# Linear_scale_digitizer.net
KiCad netlist of a schematic drawn in EAGLE
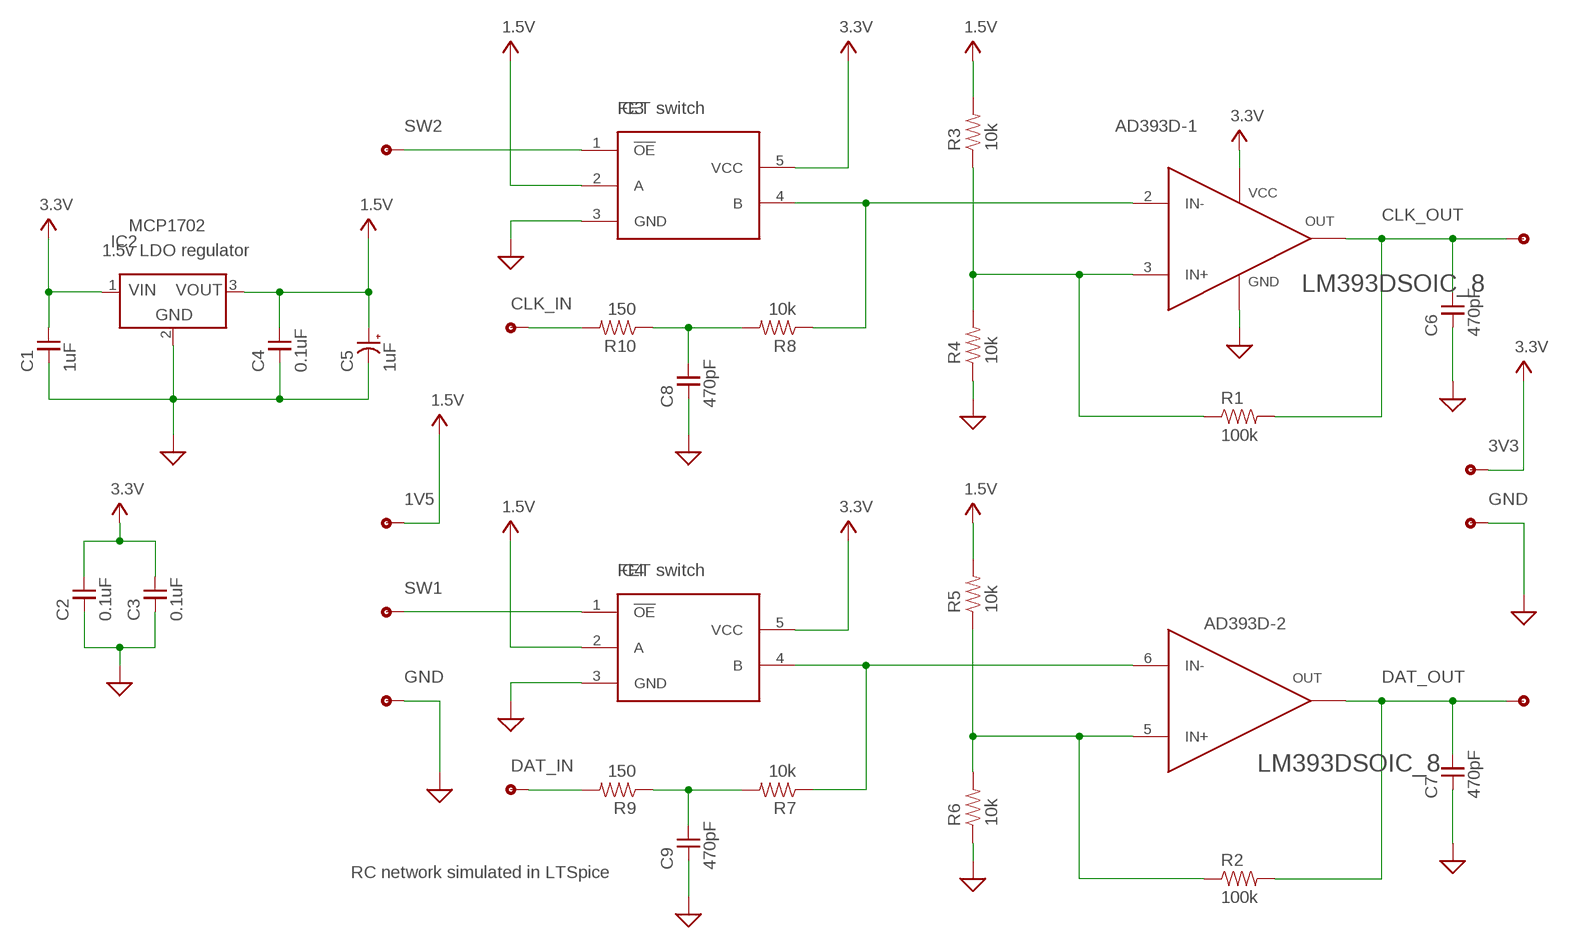
[diagram p0: schematic, sheet 1]

(export (version "E")
  (design (tool "Eeschema 10.0.6"))
  (components
    (comp (ref "C1")
      (value "1uF")
      (footprint "eagle-import:0805")
      (libsource (lib "eagle-import") (part "CAPACITOR0805"))
    )
    (comp (ref "C2")
      (value "0.1uF")
      (footprint "eagle-import:0805")
      (libsource (lib "eagle-import") (part "CAPACITOR0805"))
    )
    (comp (ref "C3")
      (value "0.1uF")
      (footprint "eagle-import:0805")
      (libsource (lib "eagle-import") (part "CAPACITOR0805"))
    )
    (comp (ref "C4")
      (value "0.1uF")
      (footprint "eagle-import:0805")
      (libsource (lib "eagle-import") (part "CAPACITOR0805"))
    )
    (comp (ref "C5")
      (value "1uF")
      (footprint "eagle-import:0805")
      (libsource (lib "eagle-import") (part "CAPACITOR+0805"))
    )
    (comp (ref "C6")
      (value "470pF")
      (footprint "eagle-import:0805")
      (libsource (lib "eagle-import") (part "CAPACITOR0805"))
    )
    (comp (ref "C7")
      (value "470pF")
      (footprint "eagle-import:0805")
      (libsource (lib "eagle-import") (part "CAPACITOR0805"))
    )
    (comp (ref "C8")
      (value "470pF")
      (footprint "eagle-import:0805")
      (libsource (lib "eagle-import") (part "CAPACITOR0805"))
    )
    (comp (ref "C9")
      (value "470pF")
      (footprint "eagle-import:0805")
      (libsource (lib "eagle-import") (part "CAPACITOR0805"))
    )
    (comp (ref "IC1")
      (value "LM393DSOIC_8")
      (footprint "eagle-import:SO_8")
      (libsource (lib "eagle-import") (part "LM393DSOIC_8"))
    )
    (comp (ref "IC2")
      (value "MCP1702")
      (footprint "eagle-import:SOT-23A")
      (libsource (lib "eagle-import") (part "MCP1702"))
    )
    (comp (ref "IC3")
      (value "SN74CB3T1G125")
      (footprint "eagle-import:SOT_23-5")
      (libsource (lib "eagle-import") (part "SN74CB3T1G125"))
    )
    (comp (ref "IC4")
      (value "SN74CB3T1G125")
      (footprint "eagle-import:SOT_23-5")
      (libsource (lib "eagle-import") (part "SN74CB3T1G125"))
    )
    (comp (ref "R1")
      (value "100k")
      (footprint "eagle-import:0805")
      (libsource (lib "eagle-import") (part "RESISTOR0805SMD"))
    )
    (comp (ref "R2")
      (value "100k")
      (footprint "eagle-import:0805")
      (libsource (lib "eagle-import") (part "RESISTOR0805SMD"))
    )
    (comp (ref "R3")
      (value "10k")
      (footprint "eagle-import:0805")
      (libsource (lib "eagle-import") (part "RESISTOR0805SMD"))
    )
    (comp (ref "R4")
      (value "10k")
      (footprint "eagle-import:0805")
      (libsource (lib "eagle-import") (part "RESISTOR0805SMD"))
    )
    (comp (ref "R5")
      (value "10k")
      (footprint "eagle-import:0805")
      (libsource (lib "eagle-import") (part "RESISTOR0805SMD"))
    )
    (comp (ref "R6")
      (value "10k")
      (footprint "eagle-import:0805")
      (libsource (lib "eagle-import") (part "RESISTOR0805SMD"))
    )
    (comp (ref "R7")
      (value "10k")
      (footprint "eagle-import:0805")
      (libsource (lib "eagle-import") (part "RESISTOR0805SMD"))
    )
    (comp (ref "R8")
      (value "10k")
      (footprint "eagle-import:0805")
      (libsource (lib "eagle-import") (part "RESISTOR0805SMD"))
    )
    (comp (ref "R9")
      (value "150")
      (footprint "eagle-import:0805")
      (libsource (lib "eagle-import") (part "RESISTOR0805SMD"))
    )
    (comp (ref "R10")
      (value "150")
      (footprint "eagle-import:0805")
      (libsource (lib "eagle-import") (part "RESISTOR0805SMD"))
    )
    (comp (ref "TP1") (value "TP") (footprint "eagle-import:TP") (libsource (lib "eagle-import") (part "TP")))
    (comp (ref "TP2") (value "TP") (footprint "eagle-import:TP") (libsource (lib "eagle-import") (part "TP")))
    (comp (ref "TP3") (value "TP") (footprint "eagle-import:TP") (libsource (lib "eagle-import") (part "TP")))
    (comp (ref "TP4") (value "TP") (footprint "eagle-import:TP") (libsource (lib "eagle-import") (part "TP")))
    (comp (ref "TP5") (value "TP") (footprint "eagle-import:TP") (libsource (lib "eagle-import") (part "TP")))
    (comp (ref "TP6") (value "TP") (footprint "eagle-import:TP") (libsource (lib "eagle-import") (part "TP")))
    (comp (ref "TP7") (value "TP") (footprint "eagle-import:TP") (libsource (lib "eagle-import") (part "TP")))
    (comp (ref "TP8") (value "TP") (footprint "eagle-import:TP") (libsource (lib "eagle-import") (part "TP")))
    (comp (ref "TP9") (value "TP") (footprint "eagle-import:TP") (libsource (lib "eagle-import") (part "TP")))
    (comp (ref "TP10")
      (value "TP")
      (footprint "eagle-import:TP")
      (libsource (lib "eagle-import") (part "TP"))
    )
  )
  (nets
    (net (code "1") (name "/CLK_IN") (class "Default")
      (node (ref "R10") (pin "2") (pinfunction "2_2") (pintype "passive"))
      (node (ref "TP5") (pin "P$1") (pinfunction "P$1_P$1") (pintype "bidirectional"))
    )
    (net (code "2") (name "/CLK_OUT") (class "Default")
      (node (ref "C6") (pin "2") (pinfunction "2_2") (pintype "passive"))
      (node (ref "IC1") (pin "1") (pinfunction "OUT_1") (pintype "bidirectional"))
      (node (ref "R1") (pin "2") (pinfunction "2_2") (pintype "passive"))
      (node (ref "TP1") (pin "P$1") (pinfunction "P$1_P$1") (pintype "bidirectional"))
    )
    (net (code "3") (name "/DAT_IN") (class "Default")
      (node (ref "R9") (pin "2") (pinfunction "2_2") (pintype "passive"))
      (node (ref "TP6") (pin "P$1") (pinfunction "P$1_P$1") (pintype "bidirectional"))
    )
    (net (code "4") (name "/DAT_OUT") (class "Default")
      (node (ref "C7") (pin "2") (pinfunction "2_2") (pintype "passive"))
      (node (ref "IC1") (pin "7") (pinfunction "OUT_7") (pintype "bidirectional"))
      (node (ref "R2") (pin "2") (pinfunction "2_2") (pintype "passive"))
      (node (ref "TP2") (pin "P$1") (pinfunction "P$1_P$1") (pintype "bidirectional"))
    )
    (net (code "5") (name "/SW1") (class "Default")
      (node (ref "IC4") (pin "1") (pinfunction "~{OE}_1") (pintype "bidirectional"))
      (node (ref "TP4") (pin "P$1") (pinfunction "P$1_P$1") (pintype "bidirectional"))
    )
    (net (code "6") (name "/SW2") (class "Default")
      (node (ref "IC3") (pin "1") (pinfunction "~{OE}_1") (pintype "bidirectional"))
      (node (ref "TP3") (pin "P$1") (pinfunction "P$1_P$1") (pintype "bidirectional"))
    )
    (net (code "7") (name "1.5V") (class "Default")
      (node (ref "C4") (pin "2") (pinfunction "2_2") (pintype "passive"))
      (node (ref "C5") (pin "1") (pinfunction "1_1") (pintype "passive"))
      (node (ref "IC2") (pin "3") (pinfunction "VOUT_3") (pintype "power_in"))
      (node (ref "IC3") (pin "2") (pinfunction "A_2") (pintype "bidirectional"))
      (node (ref "IC4") (pin "2") (pinfunction "A_2") (pintype "bidirectional"))
      (node (ref "R3") (pin "2") (pinfunction "2_2") (pintype "passive"))
      (node (ref "R5") (pin "2") (pinfunction "2_2") (pintype "passive"))
      (node (ref "TP7") (pin "P$1") (pinfunction "P$1_P$1") (pintype "bidirectional"))
    )
    (net (code "8") (name "3.3V") (class "Default")
      (node (ref "C1") (pin "2") (pinfunction "2_2") (pintype "passive"))
      (node (ref "C2") (pin "2") (pinfunction "2_2") (pintype "passive"))
      (node (ref "C3") (pin "2") (pinfunction "2_2") (pintype "passive"))
      (node (ref "IC1") (pin "8") (pinfunction "VCC_8") (pintype "bidirectional"))
      (node (ref "IC2") (pin "1") (pinfunction "VIN_1") (pintype "power_in"))
      (node (ref "IC3") (pin "5") (pinfunction "VCC_5") (pintype "bidirectional"))
      (node (ref "IC4") (pin "5") (pinfunction "VCC_5") (pintype "bidirectional"))
      (node (ref "TP10") (pin "P$1") (pinfunction "P$1_P$1") (pintype "bidirectional"))
    )
    (net (code "9") (name "AGND") (class "Default")
      (node (ref "C1") (pin "1") (pinfunction "1_1") (pintype "passive"))
      (node (ref "C2") (pin "1") (pinfunction "1_1") (pintype "passive"))
      (node (ref "C3") (pin "1") (pinfunction "1_1") (pintype "passive"))
      (node (ref "C4") (pin "1") (pinfunction "1_1") (pintype "passive"))
      (node (ref "C5") (pin "2") (pinfunction "2_2") (pintype "passive"))
      (node (ref "C6") (pin "1") (pinfunction "1_1") (pintype "passive"))
      (node (ref "C7") (pin "1") (pinfunction "1_1") (pintype "passive"))
      (node (ref "C8") (pin "1") (pinfunction "1_1") (pintype "passive"))
      (node (ref "C9") (pin "1") (pinfunction "1_1") (pintype "passive"))
      (node (ref "IC1") (pin "4") (pinfunction "GND_4") (pintype "bidirectional"))
      (node (ref "IC2") (pin "2") (pinfunction "GND_2") (pintype "power_in"))
      (node (ref "IC3") (pin "3") (pinfunction "GND_3") (pintype "bidirectional"))
      (node (ref "IC4") (pin "3") (pinfunction "GND_3") (pintype "bidirectional"))
      (node (ref "R4") (pin "1") (pinfunction "1_1") (pintype "passive"))
      (node (ref "R6") (pin "1") (pinfunction "1_1") (pintype "passive"))
      (node (ref "TP8") (pin "P$1") (pinfunction "P$1_P$1") (pintype "bidirectional"))
      (node (ref "TP9") (pin "P$1") (pinfunction "P$1_P$1") (pintype "bidirectional"))
    )
    (net (code "10") (name "Net-(C8-Pad2)") (class "Default")
      (node (ref "C8") (pin "2") (pinfunction "2_2") (pintype "passive"))
      (node (ref "R10") (pin "1") (pinfunction "1_1") (pintype "passive"))
      (node (ref "R8") (pin "2") (pinfunction "2_2") (pintype "passive"))
    )
    (net (code "11") (name "Net-(C9-Pad2)") (class "Default")
      (node (ref "C9") (pin "2") (pinfunction "2_2") (pintype "passive"))
      (node (ref "R7") (pin "2") (pinfunction "2_2") (pintype "passive"))
      (node (ref "R9") (pin "1") (pinfunction "1_1") (pintype "passive"))
    )
    (net (code "12") (name "Net-(IC1A-IN+)") (class "Default")
      (node (ref "IC1") (pin "3") (pinfunction "IN+_3") (pintype "bidirectional"))
      (node (ref "R1") (pin "1") (pinfunction "1_1") (pintype "passive"))
      (node (ref "R3") (pin "1") (pinfunction "1_1") (pintype "passive"))
      (node (ref "R4") (pin "2") (pinfunction "2_2") (pintype "passive"))
    )
    (net (code "13") (name "Net-(IC1A-IN-)") (class "Default")
      (node (ref "IC1") (pin "2") (pinfunction "IN-_2") (pintype "bidirectional"))
      (node (ref "IC3") (pin "4") (pinfunction "B_4") (pintype "bidirectional"))
      (node (ref "R8") (pin "1") (pinfunction "1_1") (pintype "passive"))
    )
    (net (code "14") (name "Net-(IC1B-IN+)") (class "Default")
      (node (ref "IC1") (pin "5") (pinfunction "IN+_5") (pintype "bidirectional"))
      (node (ref "R2") (pin "1") (pinfunction "1_1") (pintype "passive"))
      (node (ref "R5") (pin "1") (pinfunction "1_1") (pintype "passive"))
      (node (ref "R6") (pin "2") (pinfunction "2_2") (pintype "passive"))
    )
    (net (code "15") (name "Net-(IC1B-IN-)") (class "Default")
      (node (ref "IC1") (pin "6") (pinfunction "IN-_6") (pintype "bidirectional"))
      (node (ref "IC4") (pin "4") (pinfunction "B_4") (pintype "bidirectional"))
      (node (ref "R7") (pin "1") (pinfunction "1_1") (pintype "passive"))
    )
  )
)
